# Interface.net
KiCad netlist of a schematic drawn in Altium Designer
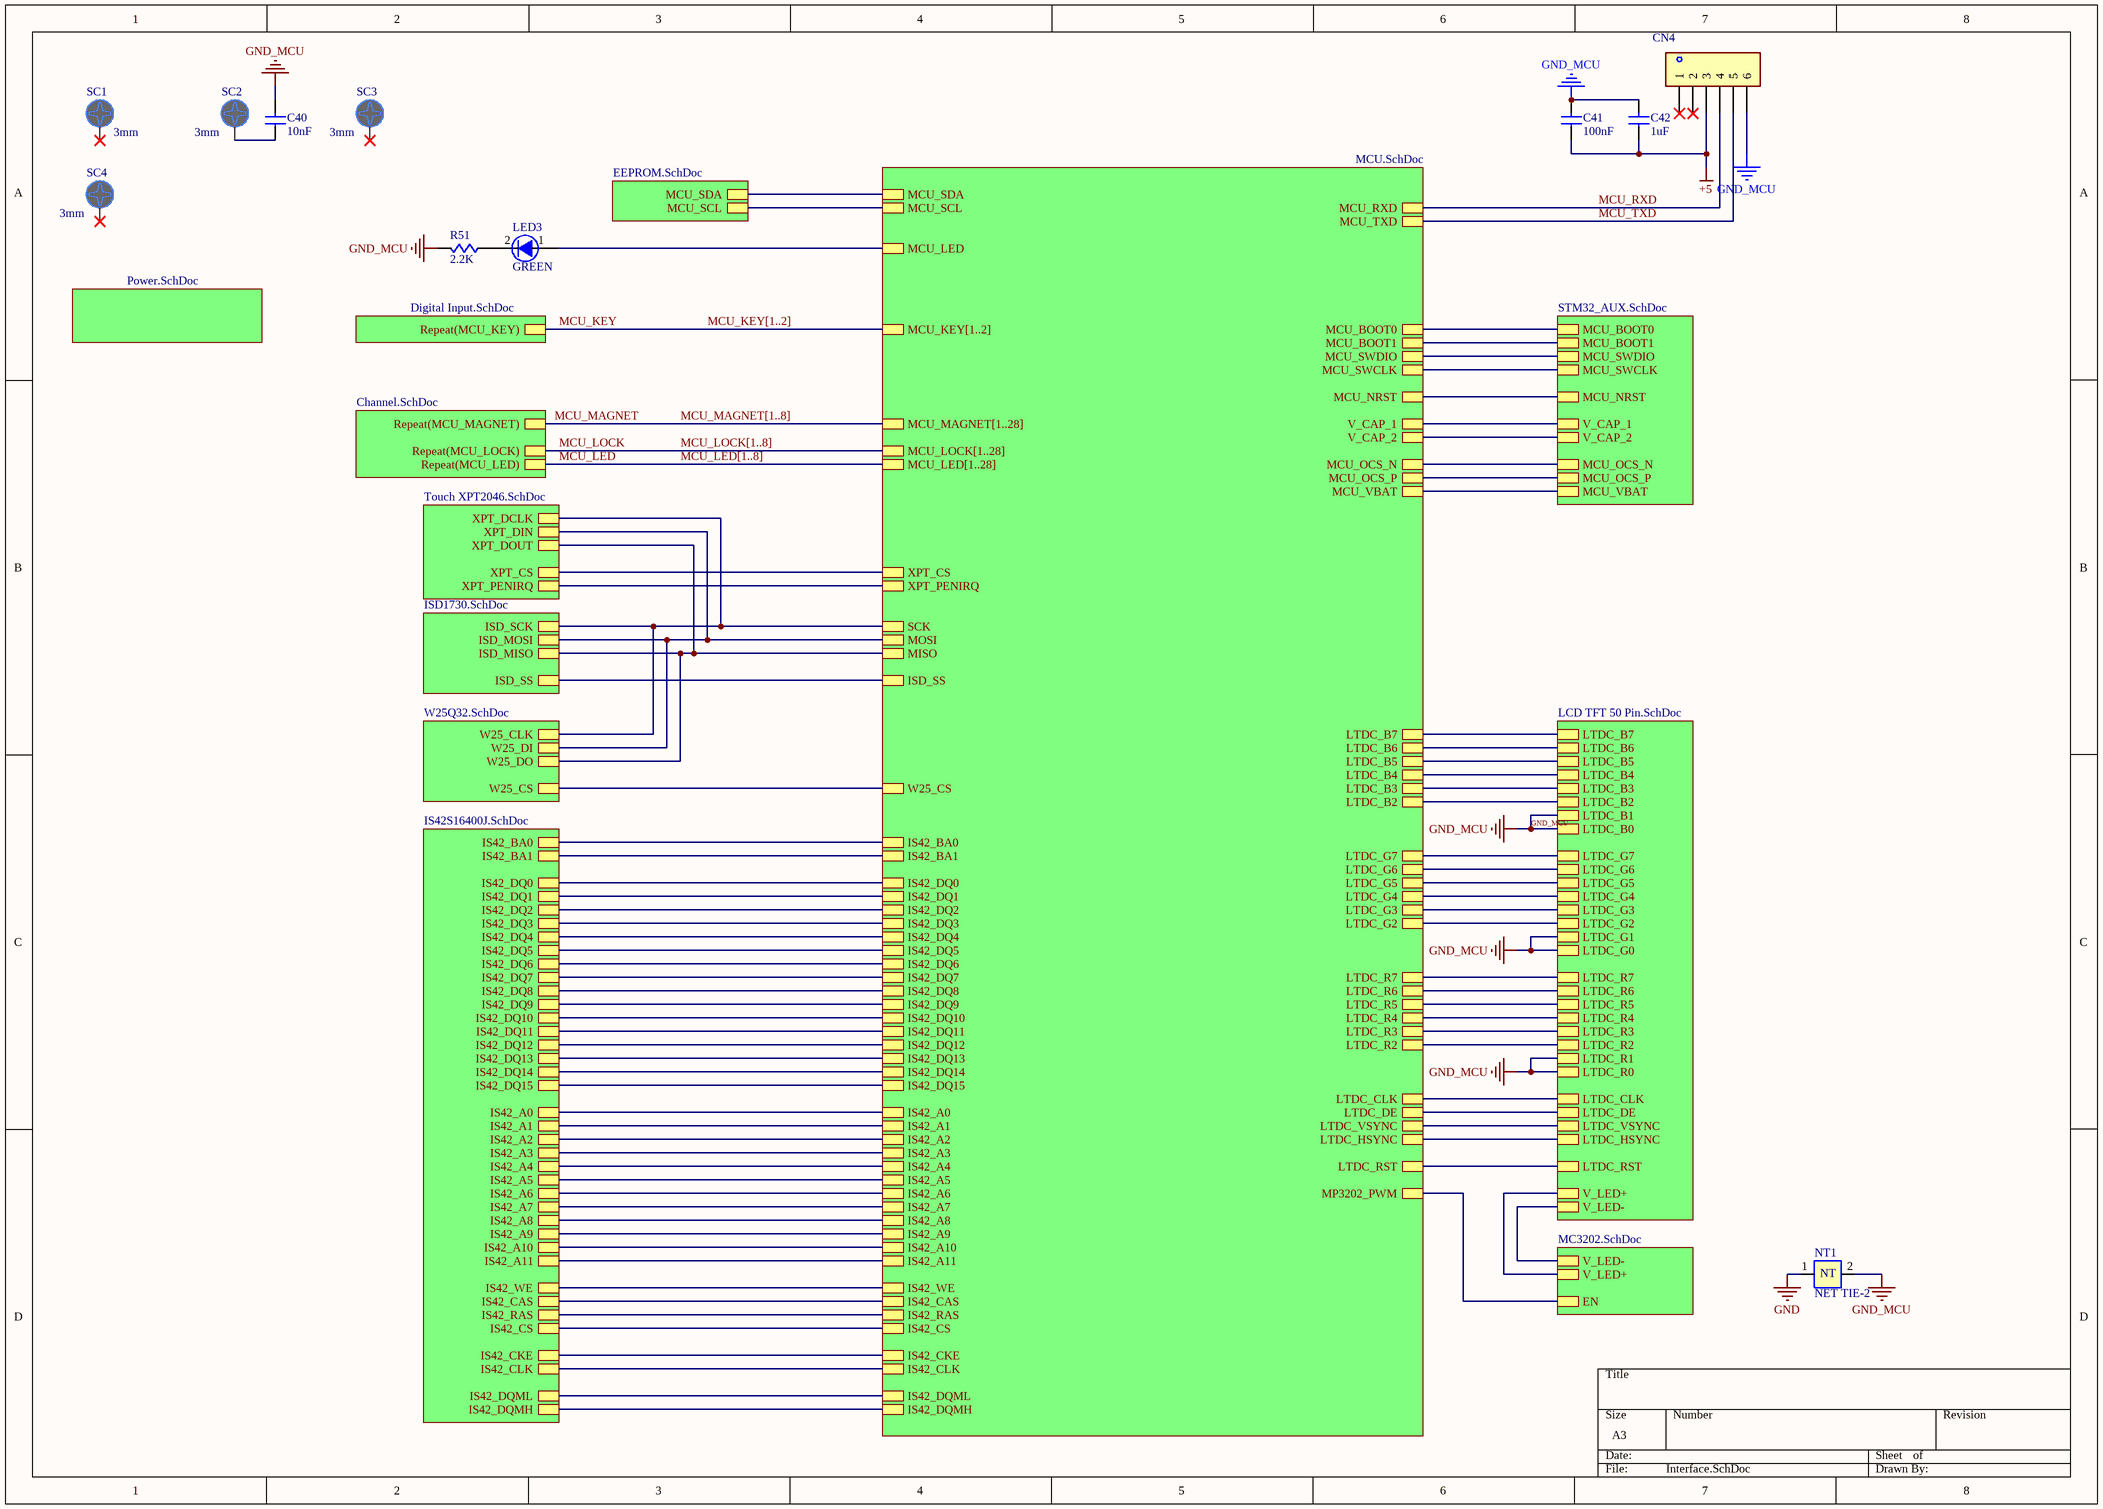
[diagram p0: Interface.SchDoc]

(export (version "E")
  (design (tool "Eeschema 10.0.6"))
  (components
    (comp (ref "C40")
      (value "10nF")
      (footprint "CAP-CER-7x2.5-Ls5")
      (description "CAPACITOR")
      (fields
        (field (name "VOLTAGE") "1KV")
        (field (name "TOLERANCE") "X7R")
        (field (name "PUBLISHER") "Mahdi Bagherzadeh")
      )
      (libsource (lib "Mahdi-Bagherzadeh") (part "CAP-CER"))
    )
    (comp (ref "C41")
      (value "100nF")
      (footprint "C-0805")
      (description "CAPACITOR")
      (fields
        (field (name "VOLTAGE") "50V")
        (field (name "TOLERANCE") "X7R")
        (field (name "PUBLISHER") "Mahdi Bagherzadeh")
      )
      (libsource (lib "Mahdi-Bagherzadeh") (part "CAP-CER"))
    )
    (comp (ref "C42")
      (value "1uF")
      (footprint "C-0805")
      (description "CAPACITOR")
      (fields
        (field (name "VOLTAGE") "50V")
        (field (name "TOLERANCE") "X7R")
        (field (name "PUBLISHER") "Mahdi Bagherzadeh")
      )
      (libsource (lib "Mahdi-Bagherzadeh") (part "CAP-CER"))
    )
    (comp (ref "CN4")
      (value "Connector XH-Straight-THD-2.54mm")
      (footprint "XH-6")
      (description "CONNECTOR")
      (fields (field (name "PUBLISHER") "Mahdi Bagherzadeh"))
      (libsource (lib "Mahdi-Bagherzadeh") (part "CN-6pin"))
    )
    (comp (ref "LED3")
      (value "LED GREEN-1206-SMD")
      (footprint "LED-1206-Y")
      (description "LED")
      (fields (field (name "COLOR") "GREEN") (field (name "PUBLISHER") "Mahdi Bagherzadeh"))
      (libsource (lib "Mahdi-Bagherzadeh") (part "LED"))
    )
    (comp (ref "NT1")
      (value "NET TIE-2")
      (footprint "NET TIE-2")
      (fields (field (name "PUBLISHER") "Mahdi Bagherzadeh"))
      (libsource (lib "Mahdi-Bagherzadeh") (part "NET TIE-2"))
    )
    (comp (ref "R51")
      (value "2.2K")
      (footprint "R-0805")
      (description "RESISTOR")
      (fields
        (field (name "TOLERANCE") "5%")
        (field (name "POWER") "1/8W")
        (field (name "PUBLISHER") "Mahdi Bagherzadeh")
      )
      (libsource (lib "Mahdi-Bagherzadeh") (part "RES"))
    )
    (comp (ref "SC1")
      (value "Screw 3mm")
      (footprint "Screw_M3")
      (description "SCREW")
      (fields (field (name "SIZE") "3mm") (field (name "PUBLISHER") "Mahdi Bagherzadeh"))
      (libsource (lib "Mahdi-Bagherzadeh") (part "SCREW"))
    )
    (comp (ref "SC2")
      (value "Screw 3mm")
      (footprint "Screw_M3")
      (description "SCREW")
      (fields (field (name "SIZE") "3mm") (field (name "PUBLISHER") "Mahdi Bagherzadeh"))
      (libsource (lib "Mahdi-Bagherzadeh") (part "SCREW"))
    )
    (comp (ref "SC3")
      (value "Screw 3mm")
      (footprint "Screw_M3")
      (description "SCREW")
      (fields (field (name "SIZE") "3mm") (field (name "PUBLISHER") "Mahdi Bagherzadeh"))
      (libsource (lib "Mahdi-Bagherzadeh") (part "SCREW"))
    )
    (comp (ref "SC4")
      (value "Screw 3mm")
      (footprint "Screw_M3")
      (description "SCREW")
      (fields (field (name "SIZE") "3mm") (field (name "PUBLISHER") "Mahdi Bagherzadeh"))
      (libsource (lib "Mahdi-Bagherzadeh") (part "SCREW"))
    )
  )
  (nets
    (net (code "25") (name "+5") (class "Default")
      (node (ref "C41") (pin "1") (pinfunction "1_1") (pintype "passive"))
      (node (ref "C42") (pin "1") (pinfunction "1_1") (pintype "passive"))
      (node (ref "CN4") (pin "3") (pinfunction "3_3") (pintype "passive"))
    )
    (net (code "97") (name "/MCU_LED_1") (class "Default")
      (node (ref "LED3") (pin "1") (pinfunction "A_1") (pintype "passive"))
    )
    (net (code "105") (name "/MCU_RXD") (class "Default")
      (node (ref "CN4") (pin "4") (pinfunction "4_4") (pintype "passive"))
    )
    (net (code "110") (name "/MCU_TXD") (class "Default")
      (node (ref "CN4") (pin "5") (pinfunction "5_5") (pintype "passive"))
    )
    (net (code "119") (name "GND") (class "Default")
      (node (ref "NT1") (pin "1") (pinfunction "1_1") (pintype "passive"))
    )
    (net (code "120") (name "GND_MCU") (class "Default")
      (node (ref "C40") (pin "2") (pinfunction "2_2") (pintype "passive"))
      (node (ref "C41") (pin "2") (pinfunction "2_2") (pintype "passive"))
      (node (ref "C42") (pin "2") (pinfunction "2_2") (pintype "passive"))
      (node (ref "CN4") (pin "6") (pinfunction "6_6") (pintype "passive"))
      (node (ref "NT1") (pin "2") (pinfunction "2_2") (pintype "passive"))
      (node (ref "R51") (pin "2") (pinfunction "2_2") (pintype "passive"))
    )
    (net (code "121") (name "Net-(C40-Pad1)") (class "Default")
      (node (ref "C40") (pin "1") (pinfunction "1_1") (pintype "passive"))
      (node (ref "SC2") (pin "1") (pinfunction "1_1") (pintype "passive"))
    )
    (net (code "122") (name "Net-(LED3-C)") (class "Default")
      (node (ref "LED3") (pin "2") (pinfunction "C_2") (pintype "passive"))
      (node (ref "R51") (pin "1") (pinfunction "1_1") (pintype "passive"))
    )
    (net (code "123") (name "unconnected-(CN4-Pad1)") (class "Default")
      (node (ref "CN4") (pin "1") (pinfunction "1_1") (pintype "passive+no_connect"))
    )
    (net (code "124") (name "unconnected-(CN4-Pad2)") (class "Default")
      (node (ref "CN4") (pin "2") (pinfunction "2_2") (pintype "passive+no_connect"))
    )
    (net (code "125") (name "unconnected-(SC1-Pad1)") (class "Default")
      (node (ref "SC1") (pin "1") (pinfunction "1_1") (pintype "passive+no_connect"))
    )
    (net (code "126") (name "unconnected-(SC3-Pad1)") (class "Default")
      (node (ref "SC3") (pin "1") (pinfunction "1_1") (pintype "passive+no_connect"))
    )
    (net (code "127") (name "unconnected-(SC4-Pad1)") (class "Default")
      (node (ref "SC4") (pin "1") (pinfunction "1_1") (pintype "passive+no_connect"))
    )
  )
)
